# HLLRT_Circuit_Full.net
KiCad netlist of a schematic drawn in EasyEDA Pro
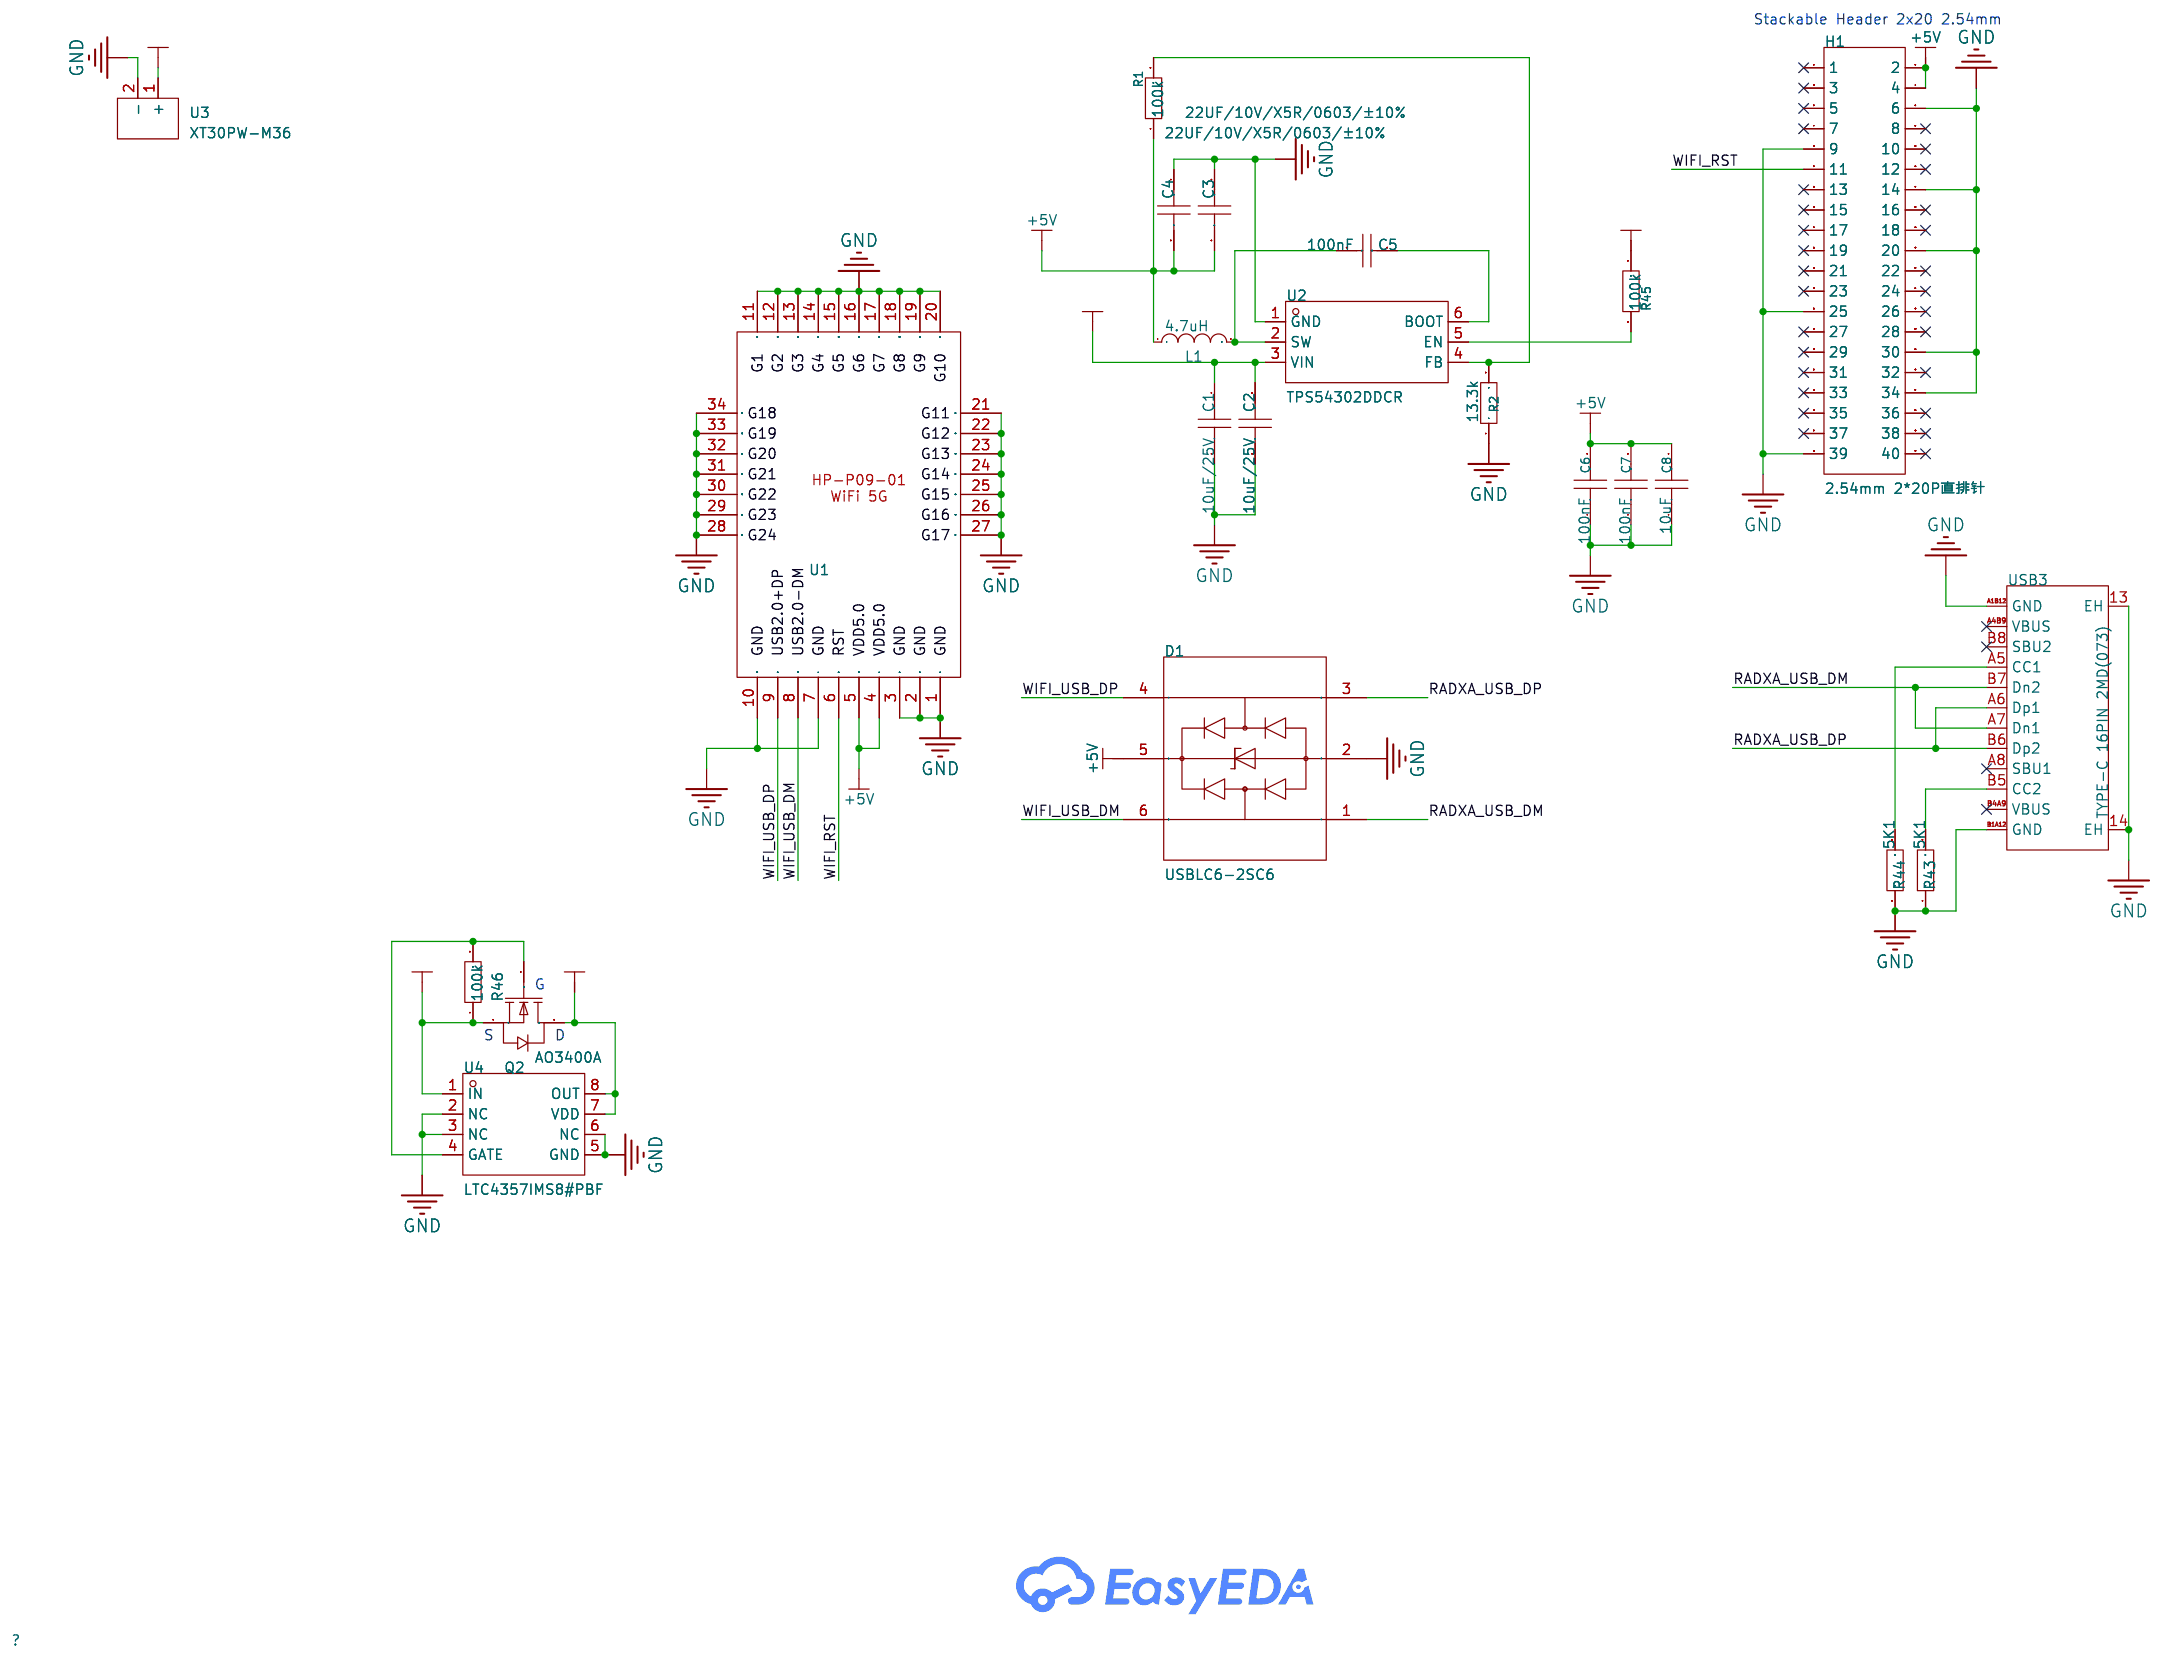
[diagram p0: schematic sheet]

(export (version "E")
  (design (tool "Eeschema 10.0.6"))
  (components
    (comp (ref "C1")
      (value "10uF/25V")
      (footprint "easyedapro:C1206")
      (description "Capacitance:47uF Tolerance:±20% Tolerance:±20% Voltage Rating:10V Temperature Coefficient:X5R")
      (fields
        (field (name "Manufacturer Part") "CL31A476MPHNNNE")
        (field (name "Manufacturer") "SAMSUNG(三星)")
      )
      (libsource (lib "easyedapro") (part "CL31A476MPHNNNE"))
    )
    (comp (ref "C2")
      (value "10uF/25V")
      (footprint "easyedapro:C1206")
      (description "Capacitance:47uF Tolerance:±20% Tolerance:±20% Voltage Rating:10V Temperature Coefficient:X5R")
      (fields
        (field (name "Manufacturer Part") "CL31A476MPHNNNE")
        (field (name "Manufacturer") "SAMSUNG(三星)")
      )
      (libsource (lib "easyedapro") (part "CL31A476MPHNNNE"))
    )
    (comp (ref "C3")
      (value "22UF/10V/X5R/0603/±10%")
      (footprint "easyedapro:C0603")
      (libsource (lib "easyedapro") (part "22UF/10V/X5R/0603/±10%"))
    )
    (comp (ref "C4")
      (value "22UF/10V/X5R/0603/±10%")
      (footprint "easyedapro:C0603")
      (libsource (lib "easyedapro") (part "22UF/10V/X5R/0603/±10%"))
    )
    (comp (ref "C5")
      (value "100nF")
      (footprint "easyedapro:C0603")
      (description "Capacitance:470pF Tolerance:±10% Tolerance:±10% Voltage Rating:50V Temperature Coefficient:X7R")
      (fields (field (name "Manufacturer Part") "0603B471K500NT") (field (name "Manufacturer") "FH(风华)"))
      (libsource (lib "easyedapro") (part "0603B471K500NT"))
    )
    (comp (ref "C6")
      (value "100nF")
      (footprint "easyedapro:C0603")
      (description "Capacitance:10uF Tolerance:±20% Tolerance:±20% Voltage Rating:25V Temperature Coefficient:X5R")
      (fields
        (field (name "Manufacturer Part") "CL10A106MA8NRNC")
        (field (name "Manufacturer") "SAMSUNG(三星)")
      )
      (libsource (lib "easyedapro") (part "CL10A106MA8NRNC"))
    )
    (comp (ref "C7")
      (value "100nF")
      (footprint "easyedapro:C0603")
      (description "Capacitance:10uF Tolerance:±20% Tolerance:±20% Voltage Rating:25V Temperature Coefficient:X5R")
      (fields
        (field (name "Manufacturer Part") "CL10A106MA8NRNC")
        (field (name "Manufacturer") "SAMSUNG(三星)")
      )
      (libsource (lib "easyedapro") (part "CL10A106MA8NRNC"))
    )
    (comp (ref "C8")
      (value "10uF")
      (footprint "easyedapro:C0603")
      (description "Capacitance:10uF Tolerance:±20% Tolerance:±20% Voltage Rating:25V Temperature Coefficient:X5R")
      (fields
        (field (name "Manufacturer Part") "CL10A106MA8NRNC")
        (field (name "Manufacturer") "SAMSUNG(三星)")
      )
      (libsource (lib "easyedapro") (part "CL10A106MA8NRNC"))
    )
    (comp (ref "D1")
      (value "USBLC6-2SC6")
      (footprint "easyedapro:SOT-23-6_L2.9-W1.6-P0.95-LS2.8-BL")
      (libsource (lib "easyedapro") (part "USBLC6-2SC6_C323793"))
    )
    (comp (ref "H1")
      (value "2.54mm 2*20P直排针")
      (footprint "easyedapro:HDR-TH_40P-P2.54-V-M-R2-C20-S2.54")
      (fields (field (name "Manufacturer") "BOOMELE(博穆精密)"))
      (libsource (lib "easyedapro") (part "Header-Male-2.54_2x20"))
    )
    (comp (ref "L1")
      (value "4.7uH")
      (footprint "easyedapro:IND-SMD_L7.3-W7.3_SCDS74T")
      (fields (field (name "Manufacturer Part") "L74R/4.7UH") (field (name "Manufacturer") "YONGYUTAI(永裕泰)"))
      (libsource (lib "easyedapro") (part "L74R/4.7UH"))
    )
    (comp (ref "Q2")
      (value "AO3400A")
      (footprint "easyedapro:SOT-23-3_L2.9-W1.3-P1.90-LS2.4-BR")
      (fields (field (name "Manufacturer") "AOS"))
      (libsource (lib "easyedapro") (part "AO3400A"))
    )
    (comp (ref "R1")
      (value "100k")
      (footprint "easyedapro:R0603")
      (fields
        (field (name "Manufacturer Part") "0603WAF2200T5E")
        (field (name "Manufacturer") "UNI-ROYAL(厚声)")
      )
      (libsource (lib "easyedapro") (part "0603WAF2200T5E"))
    )
    (comp (ref "R2")
      (value "13.3k")
      (footprint "easyedapro:R0603")
      (fields
        (field (name "Manufacturer Part") "0603WAF2200T5E")
        (field (name "Manufacturer") "UNI-ROYAL(厚声)")
      )
      (libsource (lib "easyedapro") (part "0603WAF2200T5E"))
    )
    (comp (ref "R43")
      (value "5K1")
      (footprint "easyedapro:R0603")
      (libsource (lib "easyedapro") (part "Res"))
    )
    (comp (ref "R44")
      (value "5K1")
      (footprint "easyedapro:R0603")
      (libsource (lib "easyedapro") (part "Res"))
    )
    (comp (ref "R45")
      (value "100k")
      (footprint "easyedapro:R0603")
      (fields
        (field (name "Manufacturer Part") "0603WAF2200T5E")
        (field (name "Manufacturer") "UNI-ROYAL(厚声)")
      )
      (libsource (lib "easyedapro") (part "0603WAF2200T5E"))
    )
    (comp (ref "R46")
      (value "100k")
      (footprint "easyedapro:R0603")
      (libsource (lib "easyedapro") (part "Res"))
    )
    (comp (ref "U1")
      (value "~")
      (footprint "easyedapro:HP-H01-01")
      (libsource (lib "easyedapro") (part "HP-H09-01"))
    )
    (comp (ref "U2")
      (value "TPS54302DDCR")
      (footprint "easyedapro:SOT-23-6_L2.9-W1.6-P0.95-LS2.8-BL")
      (fields (field (name "Manufacturer") "TI(德州仪器)"))
      (libsource (lib "easyedapro") (part "TPS54302DDCR_C311983"))
    )
    (comp (ref "U3")
      (value "XT30PW-M36")
      (footprint "easyedapro:CONN-TH_2P-P5.00_XT30PW-M36")
      (libsource (lib "easyedapro") (part "XT30PW-M36"))
    )
    (comp (ref "U4")
      (value "LTC4357IMS8#PBF")
      (footprint "easyedapro:MSOP-8_L3.0-W3.0-P0.65-LS5.0-BL")
      (fields (field (name "Manufacturer") "ADI(亚德诺)"))
      (libsource (lib "easyedapro") (part "LTC4357IMS8#PBF"))
    )
    (comp (ref "USB3")
      (value "TYPE-C 16PIN 2MD(073)")
      (footprint "easyedapro:USB-C-SMD_TYPE-C-16PIN-2MD-073")
      (fields (field (name "Manufacturer") "SHOU HAN(首韩)"))
      (libsource (lib "easyedapro") (part "TYPE-C 16PIN 2MD(073)"))
    )
  )
  (nets
    (net (code "1") (name "+5V") (class "Default")
      (node (ref "C3") (pin "2") (pinfunction "2_2") (pintype "unspecified"))
      (node (ref "C4") (pin "2") (pinfunction "2_2") (pintype "unspecified"))
      (node (ref "C6") (pin "2") (pinfunction "2_2") (pintype "input"))
      (node (ref "C7") (pin "2") (pinfunction "2_2") (pintype "input"))
      (node (ref "C8") (pin "2") (pinfunction "2_2") (pintype "input"))
      (node (ref "D1") (pin "5") (pinfunction "5_5") (pintype "input"))
      (node (ref "H1") (pin "2") (pinfunction "2_2") (pintype "input"))
      (node (ref "H1") (pin "4") (pinfunction "4_4") (pintype "input"))
      (node (ref "L1") (pin "1") (pinfunction "1_1") (pintype "unspecified"))
      (node (ref "R1") (pin "1") (pinfunction "1_1") (pintype "input"))
      (node (ref "U1") (pin "4") (pinfunction "4_4") (pintype "input"))
      (node (ref "U1") (pin "5") (pinfunction "5_5") (pintype "input"))
    )
    (net (code "2") (name "/RADXA_USB_DM") (class "Default")
      (node (ref "D1") (pin "1") (pinfunction "1_1") (pintype "input"))
      (node (ref "USB3") (pin "A7") (pinfunction "Dn1_A7") (pintype "unspecified"))
      (node (ref "USB3") (pin "B7") (pinfunction "Dn2_B7") (pintype "unspecified"))
    )
    (net (code "3") (name "/RADXA_USB_DP") (class "Default")
      (node (ref "D1") (pin "3") (pinfunction "3_3") (pintype "input"))
      (node (ref "USB3") (pin "A6") (pinfunction "Dp1_A6") (pintype "unspecified"))
      (node (ref "USB3") (pin "B6") (pinfunction "Dp2_B6") (pintype "unspecified"))
    )
    (net (code "4") (name "/WIFI_RST") (class "Default")
      (node (ref "H1") (pin "11") (pinfunction "11_11") (pintype "input"))
      (node (ref "U1") (pin "6") (pinfunction "6_6") (pintype "input"))
    )
    (net (code "5") (name "/WIFI_USB_DM") (class "Default")
      (node (ref "D1") (pin "6") (pinfunction "6_6") (pintype "input"))
      (node (ref "U1") (pin "8") (pinfunction "8_8") (pintype "input"))
    )
    (net (code "6") (name "/WIFI_USB_DP") (class "Default")
      (node (ref "D1") (pin "4") (pinfunction "4_4") (pintype "input"))
      (node (ref "U1") (pin "9") (pinfunction "9_9") (pintype "input"))
    )
    (net (code "7") (name "3S-4S") (class "Default")
      (node (ref "Q2") (pin "2") (pinfunction "S_2") (pintype "unspecified"))
      (node (ref "R46") (pin "1") (pinfunction "1_1") (pintype "input"))
      (node (ref "U3") (pin "1") (pinfunction "+_1") (pintype "unspecified"))
      (node (ref "U4") (pin "1") (pinfunction "IN_1") (pintype "unspecified"))
    )
    (net (code "8") (name "GND") (class "Default")
      (node (ref "C1") (pin "1") (pinfunction "1_1") (pintype "unspecified"))
      (node (ref "C2") (pin "1") (pinfunction "1_1") (pintype "unspecified"))
      (node (ref "C3") (pin "1") (pinfunction "1_1") (pintype "unspecified"))
      (node (ref "C4") (pin "1") (pinfunction "1_1") (pintype "unspecified"))
      (node (ref "C6") (pin "1") (pinfunction "1_1") (pintype "input"))
      (node (ref "C7") (pin "1") (pinfunction "1_1") (pintype "input"))
      (node (ref "C8") (pin "1") (pinfunction "1_1") (pintype "input"))
      (node (ref "D1") (pin "2") (pinfunction "2_2") (pintype "input"))
      (node (ref "H1") (pin "14") (pinfunction "14_14") (pintype "input"))
      (node (ref "H1") (pin "20") (pinfunction "20_20") (pintype "input"))
      (node (ref "H1") (pin "25") (pinfunction "25_25") (pintype "input"))
      (node (ref "H1") (pin "30") (pinfunction "30_30") (pintype "input"))
      (node (ref "H1") (pin "34") (pinfunction "34_34") (pintype "input"))
      (node (ref "H1") (pin "39") (pinfunction "39_39") (pintype "input"))
      (node (ref "H1") (pin "6") (pinfunction "6_6") (pintype "input"))
      (node (ref "H1") (pin "9") (pinfunction "9_9") (pintype "input"))
      (node (ref "R2") (pin "1") (pinfunction "1_1") (pintype "input"))
      (node (ref "R43") (pin "1") (pinfunction "1_1") (pintype "input"))
      (node (ref "R44") (pin "1") (pinfunction "1_1") (pintype "input"))
      (node (ref "U1") (pin "1") (pinfunction "1_1") (pintype "input"))
      (node (ref "U1") (pin "10") (pinfunction "10_10") (pintype "input"))
      (node (ref "U1") (pin "11") (pinfunction "11_11") (pintype "input"))
      (node (ref "U1") (pin "12") (pinfunction "12_12") (pintype "input"))
      (node (ref "U1") (pin "13") (pinfunction "13_13") (pintype "input"))
      (node (ref "U1") (pin "14") (pinfunction "14_14") (pintype "input"))
      (node (ref "U1") (pin "15") (pinfunction "15_15") (pintype "input"))
      (node (ref "U1") (pin "16") (pinfunction "16_16") (pintype "input"))
      (node (ref "U1") (pin "17") (pinfunction "17_17") (pintype "input"))
      (node (ref "U1") (pin "18") (pinfunction "18_18") (pintype "input"))
      (node (ref "U1") (pin "19") (pinfunction "19_19") (pintype "input"))
      (node (ref "U1") (pin "2") (pinfunction "2_2") (pintype "input"))
      (node (ref "U1") (pin "20") (pinfunction "20_20") (pintype "input"))
      (node (ref "U1") (pin "21") (pinfunction "21_21") (pintype "input"))
      (node (ref "U1") (pin "22") (pinfunction "22_22") (pintype "input"))
      (node (ref "U1") (pin "23") (pinfunction "23_23") (pintype "input"))
      (node (ref "U1") (pin "24") (pinfunction "24_24") (pintype "input"))
      (node (ref "U1") (pin "25") (pinfunction "25_25") (pintype "input"))
      (node (ref "U1") (pin "26") (pinfunction "26_26") (pintype "input"))
      (node (ref "U1") (pin "27") (pinfunction "27_27") (pintype "input"))
      (node (ref "U1") (pin "28") (pinfunction "28_28") (pintype "input"))
      (node (ref "U1") (pin "29") (pinfunction "29_29") (pintype "input"))
      (node (ref "U1") (pin "3") (pinfunction "3_3") (pintype "input"))
      (node (ref "U1") (pin "30") (pinfunction "30_30") (pintype "input"))
      (node (ref "U1") (pin "31") (pinfunction "31_31") (pintype "input"))
      (node (ref "U1") (pin "32") (pinfunction "32_32") (pintype "input"))
      (node (ref "U1") (pin "33") (pinfunction "33_33") (pintype "input"))
      (node (ref "U1") (pin "34") (pinfunction "34_34") (pintype "input"))
      (node (ref "U1") (pin "7") (pinfunction "7_7") (pintype "input"))
      (node (ref "U2") (pin "1") (pinfunction "GND_1") (pintype "unspecified"))
      (node (ref "U3") (pin "2") (pinfunction "-_2") (pintype "unspecified"))
      (node (ref "U4") (pin "2") (pinfunction "NC_2") (pintype "unspecified"))
      (node (ref "U4") (pin "3") (pinfunction "NC_3") (pintype "unspecified"))
      (node (ref "U4") (pin "5") (pinfunction "GND_5") (pintype "unspecified"))
      (node (ref "U4") (pin "6") (pinfunction "NC_6") (pintype "unspecified"))
      (node (ref "USB3") (pin "13") (pinfunction "EH_13") (pintype "unspecified"))
      (node (ref "USB3") (pin "14") (pinfunction "EH_14") (pintype "unspecified"))
      (node (ref "USB3") (pin "A1B12") (pinfunction "GND_A1B12") (pintype "unspecified"))
      (node (ref "USB3") (pin "B1A12") (pinfunction "GND_B1A12") (pintype "unspecified"))
    )
    (net (code "9") (name "Net-(Q2-G)") (class "Default")
      (node (ref "Q2") (pin "1") (pinfunction "G_1") (pintype "unspecified"))
      (node (ref "R46") (pin "2") (pinfunction "2_2") (pintype "input"))
      (node (ref "U4") (pin "4") (pinfunction "GATE_4") (pintype "unspecified"))
    )
    (net (code "10") (name "Net-(U2-BOOT)") (class "Default")
      (node (ref "C5") (pin "2") (pinfunction "2_2") (pintype "input"))
      (node (ref "U2") (pin "6") (pinfunction "BOOT_6") (pintype "unspecified"))
    )
    (net (code "11") (name "Net-(U2-EN)") (class "Default")
      (node (ref "R45") (pin "2") (pinfunction "2_2") (pintype "input"))
      (node (ref "U2") (pin "5") (pinfunction "EN_5") (pintype "unspecified"))
    )
    (net (code "12") (name "Net-(U2-FB)") (class "Default")
      (node (ref "R1") (pin "2") (pinfunction "2_2") (pintype "input"))
      (node (ref "R2") (pin "2") (pinfunction "2_2") (pintype "input"))
      (node (ref "U2") (pin "4") (pinfunction "FB_4") (pintype "unspecified"))
    )
    (net (code "13") (name "Net-(U2-SW)") (class "Default")
      (node (ref "C5") (pin "1") (pinfunction "1_1") (pintype "input"))
      (node (ref "L1") (pin "2") (pinfunction "2_2") (pintype "unspecified"))
      (node (ref "U2") (pin "2") (pinfunction "SW_2") (pintype "unspecified"))
    )
    (net (code "14") (name "Net-(USB3-CC1)") (class "Default")
      (node (ref "R44") (pin "2") (pinfunction "2_2") (pintype "input"))
      (node (ref "USB3") (pin "A5") (pinfunction "CC1_A5") (pintype "unspecified"))
    )
    (net (code "15") (name "Net-(USB3-CC2)") (class "Default")
      (node (ref "R43") (pin "2") (pinfunction "2_2") (pintype "input"))
      (node (ref "USB3") (pin "B5") (pinfunction "CC2_B5") (pintype "unspecified"))
    )
    (net (code "16") (name "VIN_BAT") (class "Default")
      (node (ref "C1") (pin "2") (pinfunction "2_2") (pintype "unspecified"))
      (node (ref "C2") (pin "2") (pinfunction "2_2") (pintype "unspecified"))
      (node (ref "Q2") (pin "3") (pinfunction "D_3") (pintype "unspecified"))
      (node (ref "R45") (pin "1") (pinfunction "1_1") (pintype "input"))
      (node (ref "U2") (pin "3") (pinfunction "VIN_3") (pintype "unspecified"))
      (node (ref "U4") (pin "7") (pinfunction "VDD_7") (pintype "unspecified"))
      (node (ref "U4") (pin "8") (pinfunction "OUT_8") (pintype "unspecified"))
    )
    (net (code "17") (name "unconnected-(H1-Pad1)") (class "Default")
      (node (ref "H1") (pin "1") (pinfunction "1_1") (pintype "input+no_connect"))
    )
    (net (code "18") (name "unconnected-(H1-Pad3)") (class "Default")
      (node (ref "H1") (pin "3") (pinfunction "3_3") (pintype "input+no_connect"))
    )
    (net (code "19") (name "unconnected-(H1-Pad5)") (class "Default")
      (node (ref "H1") (pin "5") (pinfunction "5_5") (pintype "input+no_connect"))
    )
    (net (code "20") (name "unconnected-(H1-Pad7)") (class "Default")
      (node (ref "H1") (pin "7") (pinfunction "7_7") (pintype "input+no_connect"))
    )
    (net (code "21") (name "unconnected-(H1-Pad8)") (class "Default")
      (node (ref "H1") (pin "8") (pinfunction "8_8") (pintype "input+no_connect"))
    )
    (net (code "22") (name "unconnected-(H1-Pad10)") (class "Default")
      (node (ref "H1") (pin "10") (pinfunction "10_10") (pintype "input+no_connect"))
    )
    (net (code "23") (name "unconnected-(H1-Pad12)") (class "Default")
      (node (ref "H1") (pin "12") (pinfunction "12_12") (pintype "input+no_connect"))
    )
    (net (code "24") (name "unconnected-(H1-Pad13)") (class "Default")
      (node (ref "H1") (pin "13") (pinfunction "13_13") (pintype "input+no_connect"))
    )
    (net (code "25") (name "unconnected-(H1-Pad15)") (class "Default")
      (node (ref "H1") (pin "15") (pinfunction "15_15") (pintype "input+no_connect"))
    )
    (net (code "26") (name "unconnected-(H1-Pad16)") (class "Default")
      (node (ref "H1") (pin "16") (pinfunction "16_16") (pintype "input+no_connect"))
    )
    (net (code "27") (name "unconnected-(H1-Pad17)") (class "Default")
      (node (ref "H1") (pin "17") (pinfunction "17_17") (pintype "input+no_connect"))
    )
    (net (code "28") (name "unconnected-(H1-Pad18)") (class "Default")
      (node (ref "H1") (pin "18") (pinfunction "18_18") (pintype "input+no_connect"))
    )
    (net (code "29") (name "unconnected-(H1-Pad19)") (class "Default")
      (node (ref "H1") (pin "19") (pinfunction "19_19") (pintype "input+no_connect"))
    )
    (net (code "30") (name "unconnected-(H1-Pad21)") (class "Default")
      (node (ref "H1") (pin "21") (pinfunction "21_21") (pintype "input+no_connect"))
    )
    (net (code "31") (name "unconnected-(H1-Pad22)") (class "Default")
      (node (ref "H1") (pin "22") (pinfunction "22_22") (pintype "input+no_connect"))
    )
    (net (code "32") (name "unconnected-(H1-Pad23)") (class "Default")
      (node (ref "H1") (pin "23") (pinfunction "23_23") (pintype "input+no_connect"))
    )
    (net (code "33") (name "unconnected-(H1-Pad24)") (class "Default")
      (node (ref "H1") (pin "24") (pinfunction "24_24") (pintype "input+no_connect"))
    )
    (net (code "34") (name "unconnected-(H1-Pad26)") (class "Default")
      (node (ref "H1") (pin "26") (pinfunction "26_26") (pintype "input+no_connect"))
    )
    (net (code "35") (name "unconnected-(H1-Pad27)") (class "Default")
      (node (ref "H1") (pin "27") (pinfunction "27_27") (pintype "input+no_connect"))
    )
    (net (code "36") (name "unconnected-(H1-Pad28)") (class "Default")
      (node (ref "H1") (pin "28") (pinfunction "28_28") (pintype "input+no_connect"))
    )
    (net (code "37") (name "unconnected-(H1-Pad29)") (class "Default")
      (node (ref "H1") (pin "29") (pinfunction "29_29") (pintype "input+no_connect"))
    )
    (net (code "38") (name "unconnected-(H1-Pad31)") (class "Default")
      (node (ref "H1") (pin "31") (pinfunction "31_31") (pintype "input+no_connect"))
    )
    (net (code "39") (name "unconnected-(H1-Pad32)") (class "Default")
      (node (ref "H1") (pin "32") (pinfunction "32_32") (pintype "input+no_connect"))
    )
    (net (code "40") (name "unconnected-(H1-Pad33)") (class "Default")
      (node (ref "H1") (pin "33") (pinfunction "33_33") (pintype "input+no_connect"))
    )
    (net (code "41") (name "unconnected-(H1-Pad35)") (class "Default")
      (node (ref "H1") (pin "35") (pinfunction "35_35") (pintype "input+no_connect"))
    )
    (net (code "42") (name "unconnected-(H1-Pad36)") (class "Default")
      (node (ref "H1") (pin "36") (pinfunction "36_36") (pintype "input+no_connect"))
    )
    (net (code "43") (name "unconnected-(H1-Pad37)") (class "Default")
      (node (ref "H1") (pin "37") (pinfunction "37_37") (pintype "input+no_connect"))
    )
    (net (code "44") (name "unconnected-(H1-Pad38)") (class "Default")
      (node (ref "H1") (pin "38") (pinfunction "38_38") (pintype "input+no_connect"))
    )
    (net (code "45") (name "unconnected-(H1-Pad40)") (class "Default")
      (node (ref "H1") (pin "40") (pinfunction "40_40") (pintype "input+no_connect"))
    )
    (net (code "46") (name "unconnected-(USB3-SBU1-PadA8)") (class "Default")
      (node (ref "USB3") (pin "A8") (pinfunction "SBU1_A8") (pintype "unspecified+no_connect"))
    )
    (net (code "47") (name "unconnected-(USB3-SBU2-PadB8)") (class "Default")
      (node (ref "USB3") (pin "B8") (pinfunction "SBU2_B8") (pintype "unspecified+no_connect"))
    )
    (net (code "48") (name "unconnected-(USB3-VBUS-PadA4B9)") (class "Default")
      (node (ref "USB3") (pin "A4B9") (pinfunction "VBUS_A4B9") (pintype "unspecified+no_connect"))
    )
    (net (code "49") (name "unconnected-(USB3-VBUS-PadB4A9)") (class "Default")
      (node (ref "USB3") (pin "B4A9") (pinfunction "VBUS_B4A9") (pintype "unspecified+no_connect"))
    )
  )
)
